# Temperature_sensor.net
KiCad netlist of a schematic drawn in Altium Designer
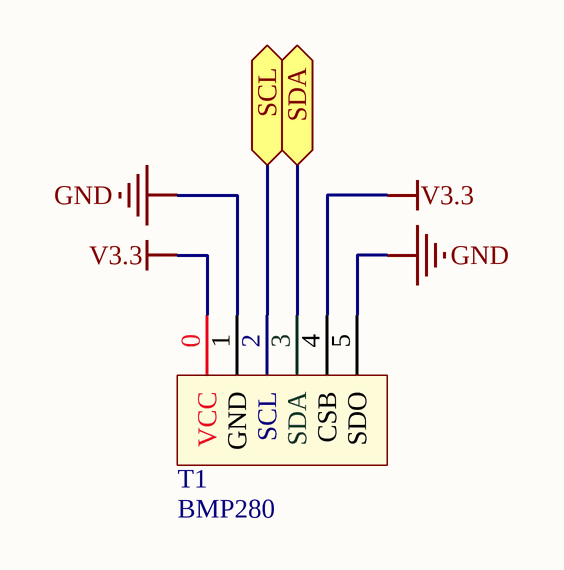
[diagram p0: Temperature_sensor.SchDoc]

(export (version "E")
  (design (tool "Eeschema 10.0.6"))
  (components
    (comp (ref "T1")
      (value "BMP280")
      (description "I2C thermometer")
      (libsource (lib "Rain_bow_Clock") (part "BMP280"))
    )
  )
  (nets
    (net (code "1") (name "/SCL") (class "Default")
      (node (ref "T1") (pin "2") (pinfunction "SCL_2") (pintype "power_in"))
    )
    (net (code "2") (name "/SDA") (class "Default")
      (node (ref "T1") (pin "3") (pinfunction "SDA_3") (pintype "power_in"))
    )
    (net (code "3") (name "GND") (class "Default")
      (node (ref "T1") (pin "1") (pinfunction "GND_1") (pintype "power_in"))
      (node (ref "T1") (pin "5") (pinfunction "SDO_5") (pintype "power_in"))
    )
    (net (code "4") (name "V3.3") (class "Default")
      (node (ref "T1") (pin "0") (pinfunction "VCC_0") (pintype "power_in"))
      (node (ref "T1") (pin "4") (pinfunction "CSB_4") (pintype "power_in"))
    )
  )
)
